# NTC_MUX.net
KiCad netlist of a schematic drawn in Altium Designer
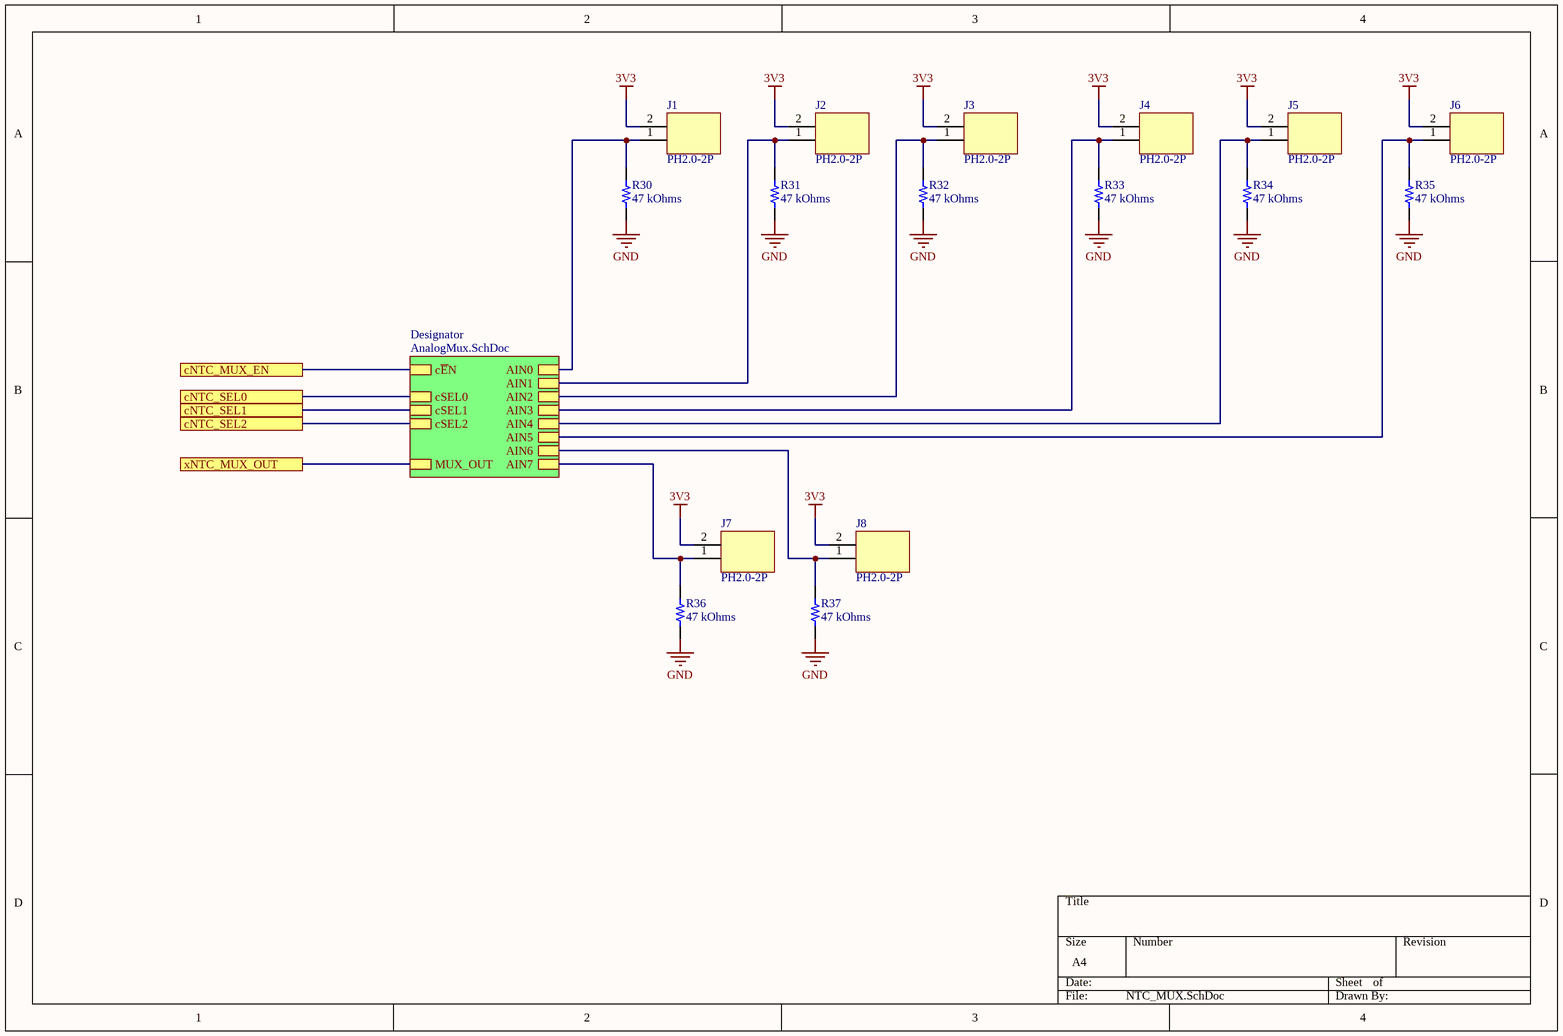
[diagram p0: NTC_MUX.SchDoc]

(export (version "E")
  (design (tool "Eeschema 10.0.6"))
  (components
    (comp (ref "J1") (value "PH2.0-2P") (footprint "PH2.0-2P") (libsource (lib "PH") (part "PH2.0-2P")))
    (comp (ref "J2") (value "PH2.0-2P") (footprint "PH2.0-2P") (libsource (lib "PH") (part "PH2.0-2P")))
    (comp (ref "J3") (value "PH2.0-2P") (footprint "PH2.0-2P") (libsource (lib "PH") (part "PH2.0-2P")))
    (comp (ref "J4") (value "PH2.0-2P") (footprint "PH2.0-2P") (libsource (lib "PH") (part "PH2.0-2P")))
    (comp (ref "J5") (value "PH2.0-2P") (footprint "PH2.0-2P") (libsource (lib "PH") (part "PH2.0-2P")))
    (comp (ref "J6") (value "PH2.0-2P") (footprint "PH2.0-2P") (libsource (lib "PH") (part "PH2.0-2P")))
    (comp (ref "J7") (value "PH2.0-2P") (footprint "PH2.0-2P") (libsource (lib "PH") (part "PH2.0-2P")))
    (comp (ref "J8") (value "PH2.0-2P") (footprint "PH2.0-2P") (libsource (lib "PH") (part "PH2.0-2P")))
    (comp (ref "R30")
      (value "47 kOhms")
      (footprint "RES 0805_2012")
      (description "RES SMD 47K OHM 0.5% 1/8W 0805")
      (fields (field (name "PART NUMBER") "RT0805DRD0747KL") (field (name "MANUFACTURER") "Yageo"))
      (libsource (lib "Celestial Altium Library - altium_library") (part "Resistor"))
    )
    (comp (ref "R31")
      (value "47 kOhms")
      (footprint "RES 0805_2012")
      (description "RES SMD 47K OHM 0.5% 1/8W 0805")
      (fields (field (name "PART NUMBER") "RT0805DRD0747KL") (field (name "MANUFACTURER") "Yageo"))
      (libsource (lib "Celestial Altium Library - altium_library") (part "Resistor"))
    )
    (comp (ref "R32")
      (value "47 kOhms")
      (footprint "RES 0805_2012")
      (description "RES SMD 47K OHM 0.5% 1/8W 0805")
      (fields (field (name "PART NUMBER") "RT0805DRD0747KL") (field (name "MANUFACTURER") "Yageo"))
      (libsource (lib "Celestial Altium Library - altium_library") (part "Resistor"))
    )
    (comp (ref "R33")
      (value "47 kOhms")
      (footprint "RES 0805_2012")
      (description "RES SMD 47K OHM 0.5% 1/8W 0805")
      (fields (field (name "PART NUMBER") "RT0805DRD0747KL") (field (name "MANUFACTURER") "Yageo"))
      (libsource (lib "Celestial Altium Library - altium_library") (part "Resistor"))
    )
    (comp (ref "R34")
      (value "47 kOhms")
      (footprint "RES 0805_2012")
      (description "RES SMD 47K OHM 0.5% 1/8W 0805")
      (fields (field (name "PART NUMBER") "RT0805DRD0747KL") (field (name "MANUFACTURER") "Yageo"))
      (libsource (lib "Celestial Altium Library - altium_library") (part "Resistor"))
    )
    (comp (ref "R35")
      (value "47 kOhms")
      (footprint "RES 0805_2012")
      (description "RES SMD 47K OHM 0.5% 1/8W 0805")
      (fields (field (name "PART NUMBER") "RT0805DRD0747KL") (field (name "MANUFACTURER") "Yageo"))
      (libsource (lib "Celestial Altium Library - altium_library") (part "Resistor"))
    )
    (comp (ref "R36")
      (value "47 kOhms")
      (footprint "RES 0805_2012")
      (description "RES SMD 47K OHM 0.5% 1/8W 0805")
      (fields (field (name "PART NUMBER") "RT0805DRD0747KL") (field (name "MANUFACTURER") "Yageo"))
      (libsource (lib "Celestial Altium Library - altium_library") (part "Resistor"))
    )
    (comp (ref "R37")
      (value "47 kOhms")
      (footprint "RES 0805_2012")
      (description "RES SMD 47K OHM 0.5% 1/8W 0805")
      (fields (field (name "PART NUMBER") "RT0805DRD0747KL") (field (name "MANUFACTURER") "Yageo"))
      (libsource (lib "Celestial Altium Library - altium_library") (part "Resistor"))
    )
  )
  (nets
    (net (code "1") (name "/AIN0") (class "Default")
      (node (ref "J1") (pin "1") (pinfunction "1_1") (pintype "passive"))
      (node (ref "R30") (pin "2") (pinfunction "2_2") (pintype "passive"))
    )
    (net (code "2") (name "/AIN1") (class "Default")
      (node (ref "J2") (pin "1") (pinfunction "1_1") (pintype "passive"))
      (node (ref "R31") (pin "2") (pinfunction "2_2") (pintype "passive"))
    )
    (net (code "3") (name "/AIN2") (class "Default")
      (node (ref "J3") (pin "1") (pinfunction "1_1") (pintype "passive"))
      (node (ref "R32") (pin "2") (pinfunction "2_2") (pintype "passive"))
    )
    (net (code "4") (name "/AIN3") (class "Default")
      (node (ref "J4") (pin "1") (pinfunction "1_1") (pintype "passive"))
      (node (ref "R33") (pin "2") (pinfunction "2_2") (pintype "passive"))
    )
    (net (code "5") (name "/AIN4") (class "Default")
      (node (ref "J5") (pin "1") (pinfunction "1_1") (pintype "passive"))
      (node (ref "R34") (pin "2") (pinfunction "2_2") (pintype "passive"))
    )
    (net (code "6") (name "/AIN5") (class "Default")
      (node (ref "J6") (pin "1") (pinfunction "1_1") (pintype "passive"))
      (node (ref "R35") (pin "2") (pinfunction "2_2") (pintype "passive"))
    )
    (net (code "7") (name "/AIN6") (class "Default")
      (node (ref "J8") (pin "1") (pinfunction "1_1") (pintype "passive"))
      (node (ref "R37") (pin "2") (pinfunction "2_2") (pintype "passive"))
    )
    (net (code "8") (name "/AIN7") (class "Default")
      (node (ref "J7") (pin "1") (pinfunction "1_1") (pintype "passive"))
      (node (ref "R36") (pin "2") (pinfunction "2_2") (pintype "passive"))
    )
    (net (code "14") (name "3V3") (class "Default")
      (node (ref "J1") (pin "2") (pinfunction "2_2") (pintype "passive"))
      (node (ref "J2") (pin "2") (pinfunction "2_2") (pintype "passive"))
      (node (ref "J3") (pin "2") (pinfunction "2_2") (pintype "passive"))
      (node (ref "J4") (pin "2") (pinfunction "2_2") (pintype "passive"))
      (node (ref "J5") (pin "2") (pinfunction "2_2") (pintype "passive"))
      (node (ref "J6") (pin "2") (pinfunction "2_2") (pintype "passive"))
      (node (ref "J7") (pin "2") (pinfunction "2_2") (pintype "passive"))
      (node (ref "J8") (pin "2") (pinfunction "2_2") (pintype "passive"))
    )
    (net (code "15") (name "GND") (class "Default")
      (node (ref "R30") (pin "1") (pinfunction "1_1") (pintype "passive"))
      (node (ref "R31") (pin "1") (pinfunction "1_1") (pintype "passive"))
      (node (ref "R32") (pin "1") (pinfunction "1_1") (pintype "passive"))
      (node (ref "R33") (pin "1") (pinfunction "1_1") (pintype "passive"))
      (node (ref "R34") (pin "1") (pinfunction "1_1") (pintype "passive"))
      (node (ref "R35") (pin "1") (pinfunction "1_1") (pintype "passive"))
      (node (ref "R36") (pin "1") (pinfunction "1_1") (pintype "passive"))
      (node (ref "R37") (pin "1") (pinfunction "1_1") (pintype "passive"))
    )
  )
)
